# TinyCube05_NoRoutes.net
KiCad netlist of a schematic drawn in EAGLE
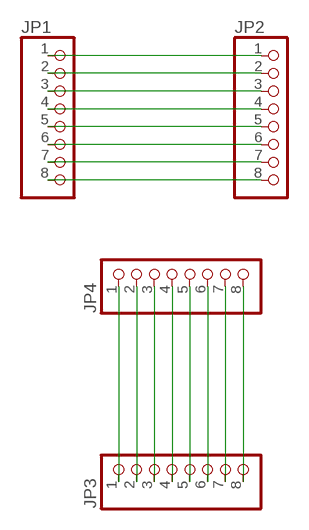
[diagram p0: schematic, sheet 1]

(export (version "E")
  (design (tool "Eeschema 10.0.6"))
  (components
    (comp (ref "JP1")
      (value "PINHD-1X8BIG")
      (footprint "eagle-import:1X08-BIG")
      (libsource (lib "eagle-import") (part "PINHD-1X8BIG"))
    )
    (comp (ref "JP2")
      (value "PINHD-1X8BIG")
      (footprint "eagle-import:1X08-BIG")
      (libsource (lib "eagle-import") (part "PINHD-1X8BIG"))
    )
    (comp (ref "JP3")
      (value "PINHD-1X8BIG")
      (footprint "eagle-import:1X08-BIG")
      (libsource (lib "eagle-import") (part "PINHD-1X8BIG"))
    )
    (comp (ref "JP4")
      (value "PINHD-1X8BIG")
      (footprint "eagle-import:1X08-BIG")
      (libsource (lib "eagle-import") (part "PINHD-1X8BIG"))
    )
  )
  (nets
    (net (code "1") (name "Net-(JP1-Pad1)") (class "Default")
      (node (ref "JP1") (pin "1") (pinfunction "1_1") (pintype "passive"))
      (node (ref "JP2") (pin "1") (pinfunction "1_1") (pintype "passive"))
    )
    (net (code "2") (name "Net-(JP1-Pad2)") (class "Default")
      (node (ref "JP1") (pin "2") (pinfunction "2_2") (pintype "passive"))
      (node (ref "JP2") (pin "2") (pinfunction "2_2") (pintype "passive"))
    )
    (net (code "3") (name "Net-(JP1-Pad3)") (class "Default")
      (node (ref "JP1") (pin "3") (pinfunction "3_3") (pintype "passive"))
      (node (ref "JP2") (pin "3") (pinfunction "3_3") (pintype "passive"))
    )
    (net (code "4") (name "Net-(JP1-Pad4)") (class "Default")
      (node (ref "JP1") (pin "4") (pinfunction "4_4") (pintype "passive"))
      (node (ref "JP2") (pin "4") (pinfunction "4_4") (pintype "passive"))
    )
    (net (code "5") (name "Net-(JP1-Pad5)") (class "Default")
      (node (ref "JP1") (pin "5") (pinfunction "5_5") (pintype "passive"))
      (node (ref "JP2") (pin "5") (pinfunction "5_5") (pintype "passive"))
    )
    (net (code "6") (name "Net-(JP1-Pad6)") (class "Default")
      (node (ref "JP1") (pin "6") (pinfunction "6_6") (pintype "passive"))
      (node (ref "JP2") (pin "6") (pinfunction "6_6") (pintype "passive"))
    )
    (net (code "7") (name "Net-(JP1-Pad7)") (class "Default")
      (node (ref "JP1") (pin "7") (pinfunction "7_7") (pintype "passive"))
      (node (ref "JP2") (pin "7") (pinfunction "7_7") (pintype "passive"))
    )
    (net (code "8") (name "Net-(JP1-Pad8)") (class "Default")
      (node (ref "JP1") (pin "8") (pinfunction "8_8") (pintype "passive"))
      (node (ref "JP2") (pin "8") (pinfunction "8_8") (pintype "passive"))
    )
    (net (code "9") (name "Net-(JP3-Pad1)") (class "Default")
      (node (ref "JP3") (pin "1") (pinfunction "1_1") (pintype "passive"))
      (node (ref "JP4") (pin "1") (pinfunction "1_1") (pintype "passive"))
    )
    (net (code "10") (name "Net-(JP3-Pad2)") (class "Default")
      (node (ref "JP3") (pin "2") (pinfunction "2_2") (pintype "passive"))
      (node (ref "JP4") (pin "2") (pinfunction "2_2") (pintype "passive"))
    )
    (net (code "11") (name "Net-(JP3-Pad3)") (class "Default")
      (node (ref "JP3") (pin "3") (pinfunction "3_3") (pintype "passive"))
      (node (ref "JP4") (pin "3") (pinfunction "3_3") (pintype "passive"))
    )
    (net (code "12") (name "Net-(JP3-Pad4)") (class "Default")
      (node (ref "JP3") (pin "4") (pinfunction "4_4") (pintype "passive"))
      (node (ref "JP4") (pin "4") (pinfunction "4_4") (pintype "passive"))
    )
    (net (code "13") (name "Net-(JP3-Pad5)") (class "Default")
      (node (ref "JP3") (pin "5") (pinfunction "5_5") (pintype "passive"))
      (node (ref "JP4") (pin "5") (pinfunction "5_5") (pintype "passive"))
    )
    (net (code "14") (name "Net-(JP3-Pad6)") (class "Default")
      (node (ref "JP3") (pin "6") (pinfunction "6_6") (pintype "passive"))
      (node (ref "JP4") (pin "6") (pinfunction "6_6") (pintype "passive"))
    )
    (net (code "15") (name "Net-(JP3-Pad7)") (class "Default")
      (node (ref "JP3") (pin "7") (pinfunction "7_7") (pintype "passive"))
      (node (ref "JP4") (pin "7") (pinfunction "7_7") (pintype "passive"))
    )
    (net (code "16") (name "Net-(JP3-Pad8)") (class "Default")
      (node (ref "JP3") (pin "8") (pinfunction "8_8") (pintype "passive"))
      (node (ref "JP4") (pin "8") (pinfunction "8_8") (pintype "passive"))
    )
  )
)
